# Connect.net
KiCad netlist of a schematic drawn in Altium Designer
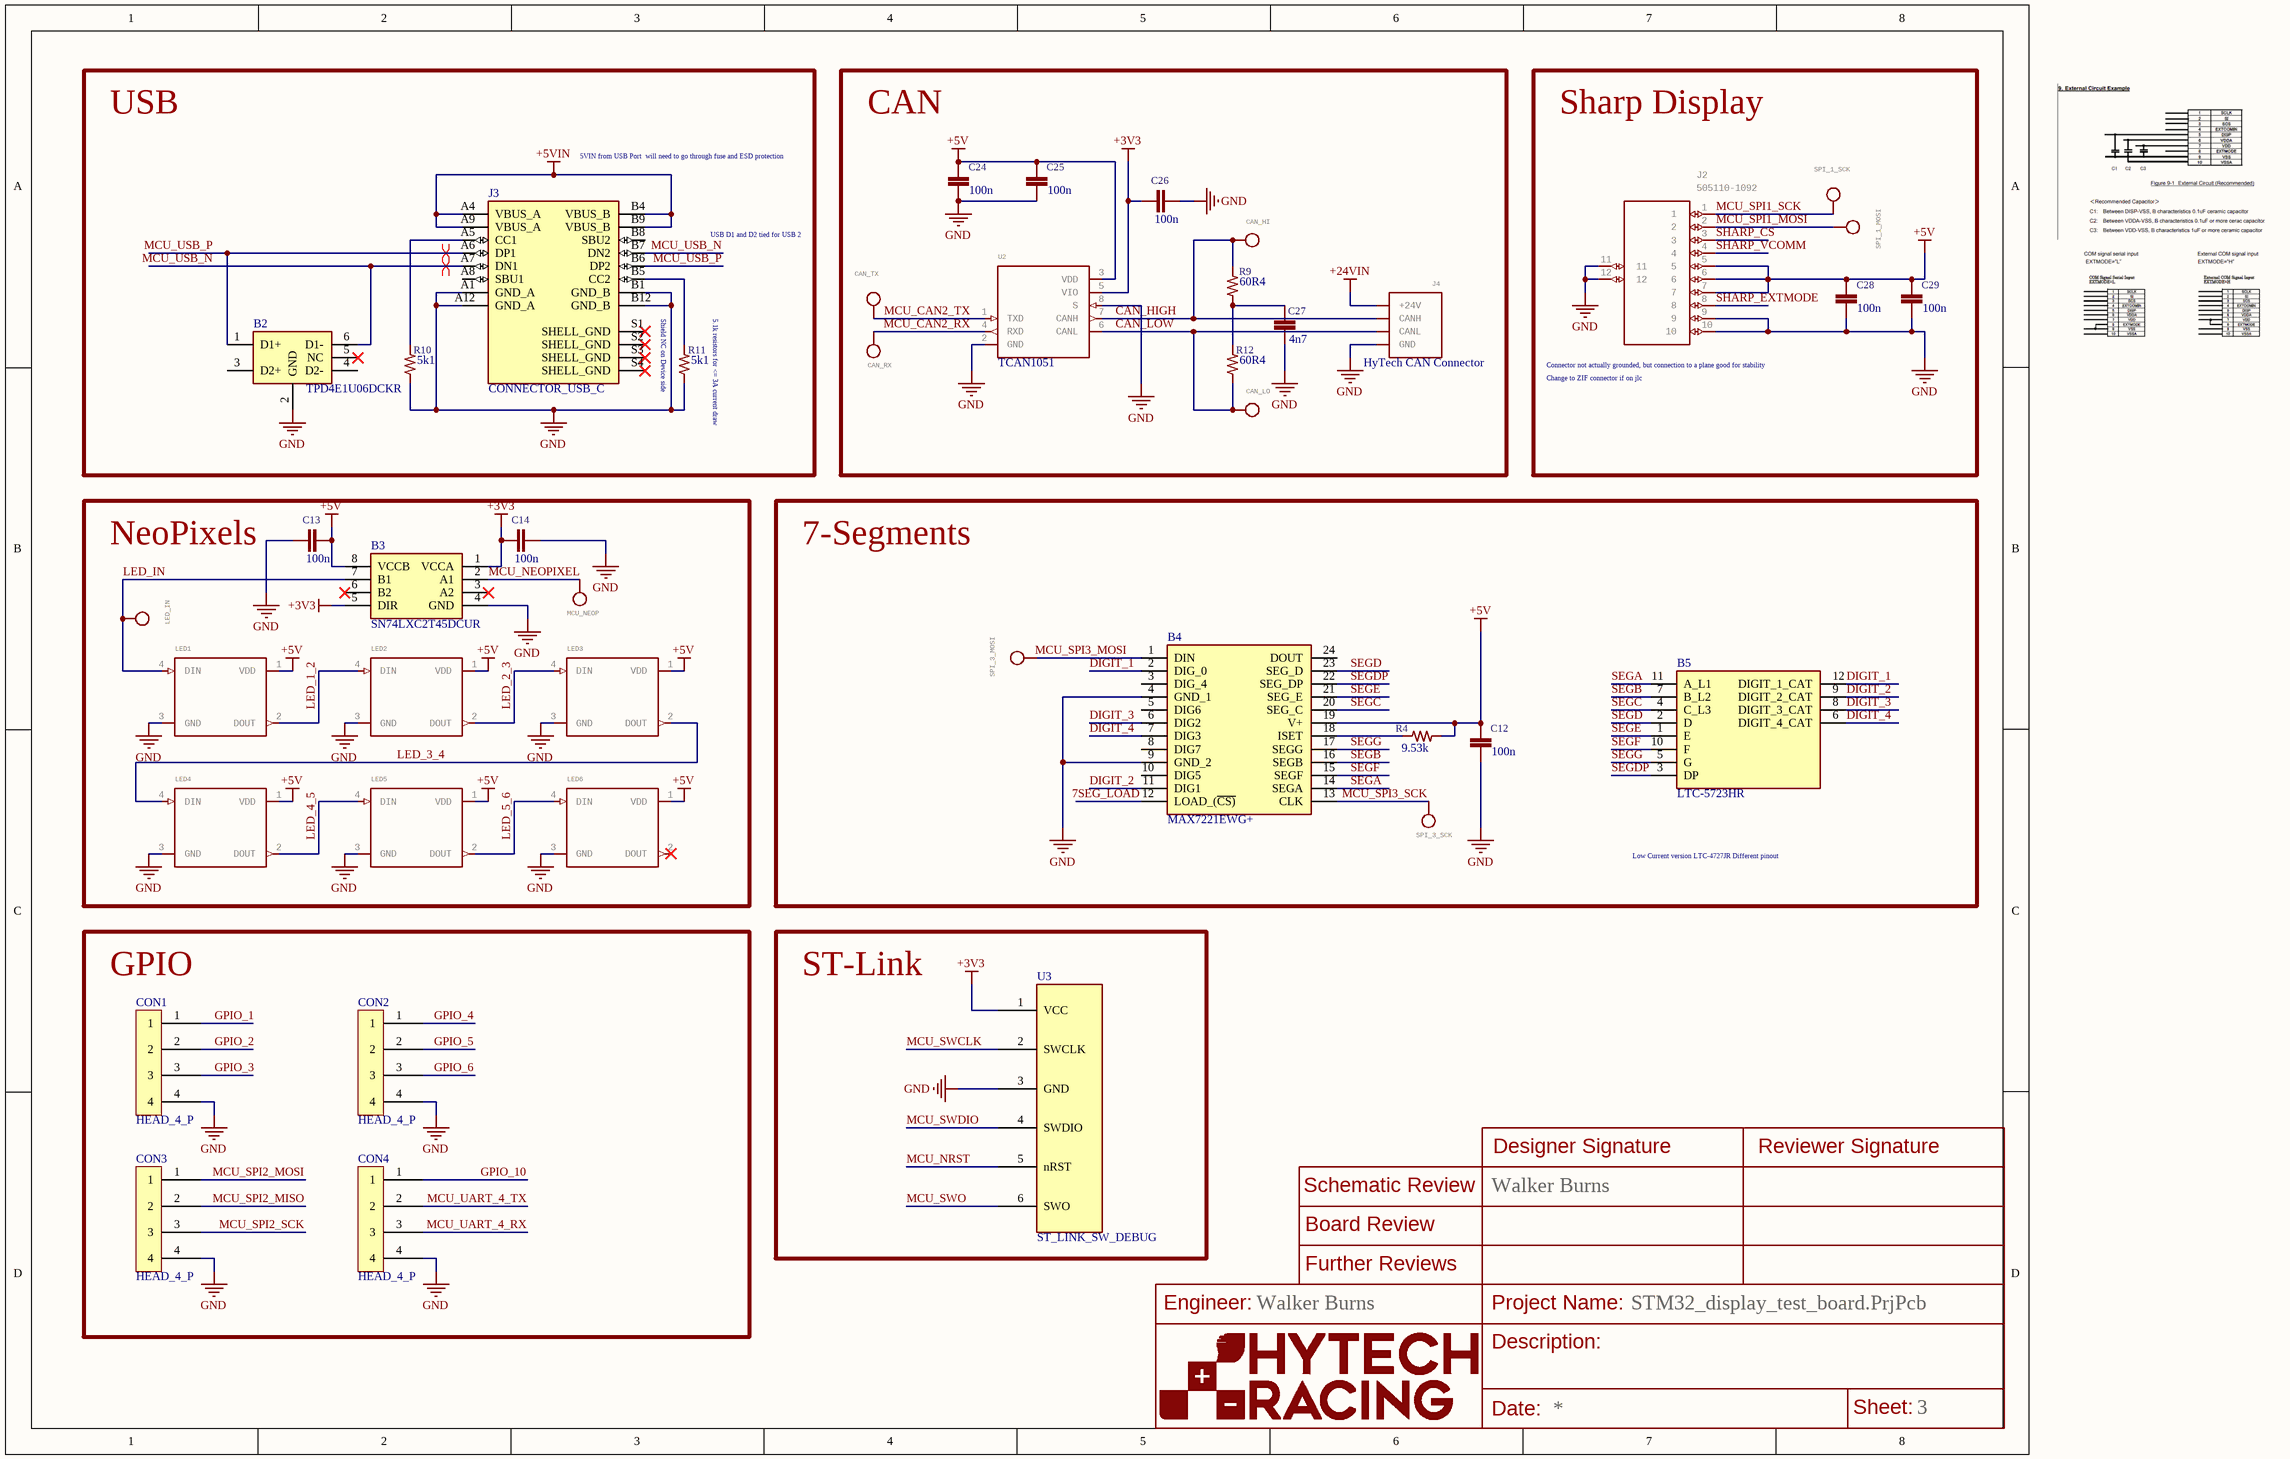
[diagram p0: Connect.SchDoc]

(export (version "E")
  (design (tool "Eeschema 10.0.6"))
  (components
    (comp (ref "B2")
      (value "TPD4E1U06DCKR")
      (footprint "SC-70-6")
      (description "Quad-Channel High-Speed ESD Protection Device")
      (fields (field (name "MOUSER PART NUMBER") "595-TPD4E1U06DCKR"))
      (libsource (lib "HyTechDevices") (part "TPD4E1U06DCKR"))
    )
    (comp (ref "B3")
      (value "SN74LXC2T45DCUR")
      (footprint "VSSOP-8")
      (fields (field (name "MOUSER PART NUMBER") "595-SN74LXC2T45DCUR"))
      (libsource (lib "HyTechDevices") (part "LEVEL_SHIFTER_3V3_TO_5V"))
    )
    (comp (ref "B4")
      (value "MAX7221EWG+")
      (footprint "SOIC-24")
      (description "MAX7221EWG+, LED Display Driver, 8-Digits 64-Segments, 4  5.5 V, 24-Pin SOIC W")
      (fields (field (name "MOUSER PART NUMBER") "700-MAX7221EWG"))
      (libsource (lib "HyTechDevices") (part "MAX7221EWG+"))
    )
    (comp (ref "B5")
      (value "LTC-5723HR")
      (footprint "7SEGMENT_DISP_12_P_TH")
      (description "LED Displays & Accessories 4 Digit, Red Normal Current, Common  Cathode")
      (fields
        (field (name "MOUSER PART NUMBER") "859-LTC-4627JR")
        (field (name "MANUFACTURER_PART_NUMBER") "LTC-4627JR")
      )
      (libsource (lib "HyTechDevices") (part "LED_7_SEGMENT_4_DIGIT"))
    )
    (comp (ref "C12")
      (value "100n")
      (footprint "0402_CAP")
      (fields
        (field (name "MANUFACTURER") "Yageo")
        (field (name "MPN") "CC0603KRX7R0BB104")
        (field (name "TOLERANCE") "10%")
      )
      (libsource (lib "HyTechDevices") (part "CAPACITOR_?_*0402"))
    )
    (comp (ref "C13")
      (value "100n")
      (footprint "0402_CAP")
      (fields
        (field (name "MANUFACTURER") "Yageo")
        (field (name "MPN") "CC0603KRX7R0BB104")
        (field (name "TOLERANCE") "10%")
      )
      (libsource (lib "") (part "CAPACITOR_?_*0402_1"))
    )
    (comp (ref "C14")
      (value "100n")
      (footprint "0402_CAP")
      (fields
        (field (name "MANUFACTURER") "Yageo")
        (field (name "MPN") "CC0603KRX7R0BB104")
        (field (name "TOLERANCE") "10%")
      )
      (libsource (lib "") (part "CAPACITOR_?_*0402_1"))
    )
    (comp (ref "C24")
      (value "100n")
      (footprint "0402_CAP")
      (fields
        (field (name "MANUFACTURER") "Yageo")
        (field (name "MPN") "CC0603KRX7R0BB104")
        (field (name "TOLERANCE") "10%")
      )
      (libsource (lib "HyTechDevices") (part "CAPACITOR_?_*0402"))
    )
    (comp (ref "C25")
      (value "100n")
      (footprint "0402_CAP")
      (fields
        (field (name "MANUFACTURER") "Yageo")
        (field (name "MPN") "CC0603KRX7R0BB104")
        (field (name "TOLERANCE") "10%")
      )
      (libsource (lib "HyTechDevices") (part "CAPACITOR_?_*0402"))
    )
    (comp (ref "C26")
      (value "100n")
      (footprint "0402_CAP")
      (fields
        (field (name "MANUFACTURER") "Yageo")
        (field (name "MPN") "CC0603KRX7R0BB104")
        (field (name "TOLERANCE") "10%")
      )
      (libsource (lib "") (part "CAPACITOR_?_*0402_1"))
    )
    (comp (ref "C27")
      (value "4n7")
      (footprint "0603-CAP")
      (fields
        (field (name "MANUFACTURER") "Yageo")
        (field (name "MPN") "CC0603KRX7R0BB104")
        (field (name "TOLERANCE") "10%")
      )
      (libsource (lib "HyTechDevices") (part "CAPACITOR_?_*0603"))
    )
    (comp (ref "C28")
      (value "100n")
      (footprint "0402_CAP")
      (fields
        (field (name "MANUFACTURER") "Yageo")
        (field (name "MPN") "CC0603KRX7R0BB104")
        (field (name "TOLERANCE") "10%")
      )
      (libsource (lib "HyTechDevices") (part "CAPACITOR_?_*0402"))
    )
    (comp (ref "C29")
      (value "100n")
      (footprint "0402_CAP")
      (fields
        (field (name "MANUFACTURER") "Yageo")
        (field (name "MPN") "CC0603KRX7R0BB104")
        (field (name "TOLERANCE") "10%")
      )
      (libsource (lib "HyTechDevices") (part "CAPACITOR_?_*0402"))
    )
    (comp (ref "CAN_HI")
      (value "Test Point for Probing")
      (footprint "5015")
      (fields (field (name "MANUFACTURER") "Keystone Electronics") (field (name "MPN") "5015"))
      (libsource (lib "HyTechDevices") (part "TEST_POINT"))
    )
    (comp (ref "CAN_LO")
      (value "Test Point for Probing")
      (footprint "5015")
      (fields (field (name "MANUFACTURER") "Keystone Electronics") (field (name "MPN") "5015"))
      (libsource (lib "HyTechDevices") (part "TEST_POINT"))
    )
    (comp (ref "CAN_RX")
      (value "Test Point for Probing")
      (footprint "5015")
      (fields (field (name "MANUFACTURER") "Keystone Electronics") (field (name "MPN") "5015"))
      (libsource (lib "HyTechDevices") (part "TEST_POINT"))
    )
    (comp (ref "CAN_TX")
      (value "Test Point for Probing")
      (footprint "5015")
      (fields (field (name "MANUFACTURER") "Keystone Electronics") (field (name "MPN") "5015"))
      (libsource (lib "HyTechDevices") (part "TEST_POINT"))
    )
    (comp (ref "CON1")
      (value "HEAD_4_P")
      (footprint "1X04")
      (description "4 Pin Standard Header")
      (libsource (lib "HyTechDevices") (part "CONNECTOR_HEADER_4"))
    )
    (comp (ref "CON2")
      (value "HEAD_4_P")
      (footprint "1X04")
      (description "4 Pin Standard Header")
      (libsource (lib "HyTechDevices") (part "CONNECTOR_HEADER_4"))
    )
    (comp (ref "CON3")
      (value "HEAD_4_P")
      (footprint "1X04")
      (description "4 Pin Standard Header")
      (libsource (lib "HyTechDevices") (part "CONNECTOR_HEADER_4"))
    )
    (comp (ref "CON4")
      (value "HEAD_4_P")
      (footprint "1X04")
      (description "4 Pin Standard Header")
      (libsource (lib "HyTechDevices") (part "CONNECTOR_HEADER_4"))
    )
    (comp (ref "FRAME3")
      (value "HyTech Racing Frame (ANSI Size A)  Prints on US Letter Landscape 8.5\" by 11\"   Fill Engineer/Description Fields with Text using the following settings:  Size: 0.1  Ratio: 8%  Line Distance: 50%  Font: Proportional  Layer: 94 Symbol")
      (fields (field (name "LIBRARYNAME") "HyTechFrames"))
      (libsource (lib "HyTechFrames") (part "FRAME"))
    )
    (comp (ref "J2")
      (value "505110-1092")
      (footprint "MOLEX_FPC_CLAMSHELL_10")
      (fields (field (name "MOUSER_PART_NUMBER") "538-505110-1092"))
      (libsource (lib "HyTechDevices") (part "CONNECTOR-10_MOLEX_FPC_CLAMSHELL"))
    )
    (comp (ref "J3")
      (value "CONNECTOR_USB_C")
      (footprint "VALCON_USB_C")
      (description "CSP-USC16-TR Valcon USB Type C Surface Mount PCB Socket")
      (fields (field (name "MF") "Valcon") (field (name "MP") "CSP-USC16-TR"))
      (libsource (lib "HyTechDevices") (part "CONNECTOR_USB_C"))
    )
    (comp (ref "J4")
      (value "HyTech CAN Connector")
      (footprint "MOLEX_MICROFIT_SMD_RIGHTANGLE_04_DUAL")
      (fields (field (name "MANUFACTURER") "Molex") (field (name "MPN") "0430450411"))
      (libsource (lib "HyTechDevices") (part "CONNECTOR-CAN_?_*μF_S_RA"))
    )
    (comp (ref "LED1")
      (value "IN-PI55QATPRPGPBPW-40  Neopixel RGBW LED  Datasheet")
      (footprint "NEOPIXEL")
      (fields (field (name "MANUFACTURER") "Inolux") (field (name "MPN") "IN-PI55QATPRPGPBPW-40"))
      (libsource (lib "HyTechDevices") (part "NEOPIXEL_*IN-PI55QATPRPGPBPW-40"))
    )
    (comp (ref "LED2")
      (value "IN-PI55QATPRPGPBPW-40  Neopixel RGBW LED  Datasheet")
      (footprint "NEOPIXEL")
      (fields (field (name "MANUFACTURER") "Inolux") (field (name "MPN") "IN-PI55QATPRPGPBPW-40"))
      (libsource (lib "HyTechDevices") (part "NEOPIXEL_*IN-PI55QATPRPGPBPW-40"))
    )
    (comp (ref "LED3")
      (value "IN-PI55QATPRPGPBPW-40  Neopixel RGBW LED  Datasheet")
      (footprint "NEOPIXEL")
      (fields (field (name "MANUFACTURER") "Inolux") (field (name "MPN") "IN-PI55QATPRPGPBPW-40"))
      (libsource (lib "HyTechDevices") (part "NEOPIXEL_*IN-PI55QATPRPGPBPW-40"))
    )
    (comp (ref "LED4")
      (value "IN-PI55QATPRPGPBPW-40  Neopixel RGBW LED  Datasheet")
      (footprint "NEOPIXEL")
      (fields (field (name "MANUFACTURER") "Inolux") (field (name "MPN") "IN-PI55QATPRPGPBPW-40"))
      (libsource (lib "HyTechDevices") (part "NEOPIXEL_*IN-PI55QATPRPGPBPW-40"))
    )
    (comp (ref "LED5")
      (value "IN-PI55QATPRPGPBPW-40  Neopixel RGBW LED  Datasheet")
      (footprint "NEOPIXEL")
      (fields (field (name "MANUFACTURER") "Inolux") (field (name "MPN") "IN-PI55QATPRPGPBPW-40"))
      (libsource (lib "HyTechDevices") (part "NEOPIXEL_*IN-PI55QATPRPGPBPW-40"))
    )
    (comp (ref "LED6")
      (value "IN-PI55QATPRPGPBPW-40  Neopixel RGBW LED  Datasheet")
      (footprint "NEOPIXEL")
      (fields (field (name "MANUFACTURER") "Inolux") (field (name "MPN") "IN-PI55QATPRPGPBPW-40"))
      (libsource (lib "HyTechDevices") (part "NEOPIXEL_*IN-PI55QATPRPGPBPW-40"))
    )
    (comp (ref "LED_IN")
      (value "Test Point for Probing")
      (footprint "5015")
      (fields (field (name "MANUFACTURER") "Keystone Electronics") (field (name "MPN") "5015"))
      (libsource (lib "HyTechDevices") (part "TEST_POINT"))
    )
    (comp (ref "MCU_NEOP")
      (value "Test Point for Probing")
      (footprint "5015")
      (fields (field (name "MANUFACTURER") "Keystone Electronics") (field (name "MPN") "5015"))
      (libsource (lib "HyTechDevices") (part "TEST_POINT"))
    )
    (comp (ref "R4")
      (value "9.53k")
      (footprint "0603-RES")
      (fields
        (field (name "MANUFACTURER") "Yageo")
        (field (name "MPN") "RC0603FR-070RL")
        (field (name "POWER") "0.1W")
      )
      (libsource (lib "HyTechDevices") (part "RESISTOR_?_*0603"))
    )
    (comp (ref "R9")
      (value "60R4")
      (footprint "0603-RES")
      (fields
        (field (name "MANUFACTURER") "Yageo")
        (field (name "MPN") "RC0603FR-070RL")
        (field (name "POWER") "0.1W")
      )
      (libsource (lib "") (part "RESISTOR_?_*0603_1"))
    )
    (comp (ref "R10")
      (value "5k1")
      (footprint "0603-RES")
      (fields
        (field (name "MANUFACTURER") "Yageo")
        (field (name "MPN") "RC0603FR-070RL")
        (field (name "POWER") "0.1W")
      )
      (libsource (lib "") (part "RESISTOR_?_*0603_1"))
    )
    (comp (ref "R11")
      (value "5k1")
      (footprint "0603-RES")
      (fields
        (field (name "MANUFACTURER") "Yageo")
        (field (name "MPN") "RC0603FR-070RL")
        (field (name "POWER") "0.1W")
      )
      (libsource (lib "") (part "RESISTOR_?_*0603_1"))
    )
    (comp (ref "R12")
      (value "60R4")
      (footprint "0603-RES")
      (fields
        (field (name "MANUFACTURER") "Yageo")
        (field (name "MPN") "RC0603FR-070RL")
        (field (name "POWER") "0.1W")
      )
      (libsource (lib "") (part "RESISTOR_?_*0603_1"))
    )
    (comp (ref "SPI_1_MOSI")
      (value "Test Point for Probing")
      (footprint "5015")
      (fields (field (name "MANUFACTURER") "Keystone Electronics") (field (name "MPN") "5015"))
      (libsource (lib "HyTechDevices") (part "TEST_POINT"))
    )
    (comp (ref "SPI_1_SCK")
      (value "Test Point for Probing")
      (footprint "5015")
      (fields (field (name "MANUFACTURER") "Keystone Electronics") (field (name "MPN") "5015"))
      (libsource (lib "HyTechDevices") (part "TEST_POINT"))
    )
    (comp (ref "SPI_3_MOSI")
      (value "Test Point for Probing")
      (footprint "5015")
      (fields (field (name "MANUFACTURER") "Keystone Electronics") (field (name "MPN") "5015"))
      (libsource (lib "HyTechDevices") (part "TEST_POINT"))
    )
    (comp (ref "SPI_3_SCK")
      (value "Test Point for Probing")
      (footprint "5015")
      (fields (field (name "MANUFACTURER") "Keystone Electronics") (field (name "MPN") "5015"))
      (libsource (lib "HyTechDevices") (part "TEST_POINT"))
    )
    (comp (ref "U2")
      (value "TCAN1051")
      (footprint "SOIC-08(NARROW,0-15\")")
      (fields (field (name "MANUFACTURER") "Texas Instruments") (field (name "MPN") "TCAN1051HGVDRQ1"))
      (libsource (lib "HyTechDevices") (part "TCAN1051*V-Q1"))
    )
    (comp (ref "U3")
      (value "ST_LINK_SW_DEBUG")
      (footprint "HEADER_6_P")
      (libsource (lib "HyTechDevices") (part "CONNECTOR_ST_LINK"))
    )
  )
  (nets
    (net (code "1") (name "+3V3") (class "Default")
      (node (ref "B3") (pin "1") (pinfunction "VCCA_1") (pintype "passive"))
      (node (ref "B3") (pin "5") (pinfunction "DIR_5") (pintype "passive"))
      (node (ref "C14") (pin "2") (pinfunction "2_2") (pintype "passive"))
      (node (ref "C26") (pin "2") (pinfunction "2_2") (pintype "passive"))
      (node (ref "U2") (pin "5") (pinfunction "VIO_5") (pintype "power_in"))
      (node (ref "U3") (pin "1") (pinfunction "VCC_1") (pintype "passive"))
    )
    (net (code "2") (name "+5V") (class "Default")
      (node (ref "B3") (pin "8") (pinfunction "VCCB_8") (pintype "passive"))
      (node (ref "B4") (pin "19") (pinfunction "V+_19") (pintype "passive"))
      (node (ref "C12") (pin "2") (pinfunction "2_2") (pintype "passive"))
      (node (ref "C13") (pin "1") (pinfunction "1_1") (pintype "passive"))
      (node (ref "C24") (pin "2") (pinfunction "2_2") (pintype "passive"))
      (node (ref "C25") (pin "2") (pinfunction "2_2") (pintype "passive"))
      (node (ref "C28") (pin "2") (pinfunction "2_2") (pintype "passive"))
      (node (ref "C29") (pin "2") (pinfunction "2_2") (pintype "passive"))
      (node (ref "J2") (pin "5") (pinfunction "5_5") (pintype "bidirectional"))
      (node (ref "J2") (pin "6") (pinfunction "6_6") (pintype "bidirectional"))
      (node (ref "J2") (pin "7") (pinfunction "7_7") (pintype "bidirectional"))
      (node (ref "LED1") (pin "1") (pinfunction "VDD_1") (pintype "power_in"))
      (node (ref "LED2") (pin "1") (pinfunction "VDD_1") (pintype "power_in"))
      (node (ref "LED3") (pin "1") (pinfunction "VDD_1") (pintype "power_in"))
      (node (ref "LED4") (pin "1") (pinfunction "VDD_1") (pintype "power_in"))
      (node (ref "LED5") (pin "1") (pinfunction "VDD_1") (pintype "power_in"))
      (node (ref "LED6") (pin "1") (pinfunction "VDD_1") (pintype "power_in"))
      (node (ref "R4") (pin "2") (pinfunction "2_2") (pintype "passive"))
      (node (ref "U2") (pin "3") (pinfunction "VDD_3") (pintype "power_in"))
    )
    (net (code "3") (name "+5VIN") (class "Default")
      (node (ref "J3") (pin "A4") (pinfunction "VBUS_A_A4") (pintype "power_in"))
      (node (ref "J3") (pin "A9") (pinfunction "VBUS_A_A9") (pintype "power_in"))
      (node (ref "J3") (pin "B4") (pinfunction "VBUS_B_B4") (pintype "power_in"))
      (node (ref "J3") (pin "B9") (pinfunction "VBUS_B_B9") (pintype "power_in"))
    )
    (net (code "4") (name "+24VIN") (class "Default")
      (node (ref "J4") (pin "1") (pinfunction "+24V_1") (pintype "power_in"))
    )
    (net (code "5") (name "/7SEG_LOAD") (class "Default")
      (node (ref "B4") (pin "12") (pinfunction "LOAD_(~{CS)}_12") (pintype "passive"))
    )
    (net (code "6") (name "/CAN_HIGH") (class "Default")
      (node (ref "CAN_HI") (pin "1") (pinfunction "1_1") (pintype "passive"))
      (node (ref "J4") (pin "4") (pinfunction "CANH_4") (pintype "bidirectional"))
      (node (ref "R9") (pin "1") (pinfunction "1_1") (pintype "passive"))
      (node (ref "U2") (pin "7") (pinfunction "CANH_7") (pintype "output"))
    )
    (net (code "7") (name "/CAN_LOW") (class "Default")
      (node (ref "CAN_LO") (pin "1") (pinfunction "1_1") (pintype "passive"))
      (node (ref "J4") (pin "3") (pinfunction "CANL_3") (pintype "bidirectional"))
      (node (ref "R12") (pin "2") (pinfunction "2_2") (pintype "passive"))
      (node (ref "U2") (pin "6") (pinfunction "CANL_6") (pintype "bidirectional"))
    )
    (net (code "8") (name "/DIGIT_1") (class "Default")
      (node (ref "B4") (pin "2") (pinfunction "DIG_0_2") (pintype "passive"))
      (node (ref "B5") (pin "12") (pinfunction "DIGIT_1_CAT_12") (pintype "passive"))
    )
    (net (code "9") (name "/DIGIT_2") (class "Default")
      (node (ref "B4") (pin "11") (pinfunction "DIG1_11") (pintype "passive"))
      (node (ref "B5") (pin "9") (pinfunction "DIGIT_2_CAT_9") (pintype "passive"))
    )
    (net (code "10") (name "/DIGIT_3") (class "Default")
      (node (ref "B4") (pin "6") (pinfunction "DIG2_6") (pintype "passive"))
      (node (ref "B5") (pin "8") (pinfunction "DIGIT_3_CAT_8") (pintype "passive"))
    )
    (net (code "11") (name "/DIGIT_4") (class "Default")
      (node (ref "B4") (pin "7") (pinfunction "DIG3_7") (pintype "passive"))
      (node (ref "B5") (pin "6") (pinfunction "DIGIT_4_CAT_6") (pintype "passive"))
    )
    (net (code "12") (name "/GPIO_1") (class "Default")
      (node (ref "CON1") (pin "1") (pinfunction "1_1") (pintype "passive"))
    )
    (net (code "13") (name "/GPIO_2") (class "Default")
      (node (ref "CON1") (pin "2") (pinfunction "2_2") (pintype "passive"))
    )
    (net (code "14") (name "/GPIO_3") (class "Default")
      (node (ref "CON1") (pin "3") (pinfunction "3_3") (pintype "passive"))
    )
    (net (code "15") (name "/GPIO_4") (class "Default")
      (node (ref "CON2") (pin "1") (pinfunction "1_1") (pintype "passive"))
    )
    (net (code "16") (name "/GPIO_5") (class "Default")
      (node (ref "CON2") (pin "2") (pinfunction "2_2") (pintype "passive"))
    )
    (net (code "17") (name "/GPIO_6") (class "Default")
      (node (ref "CON2") (pin "3") (pinfunction "3_3") (pintype "passive"))
    )
    (net (code "18") (name "/GPIO_10") (class "Default")
      (node (ref "CON4") (pin "1") (pinfunction "1_1") (pintype "passive"))
    )
    (net (code "19") (name "/LED_1_2") (class "Default")
      (node (ref "LED1") (pin "2") (pinfunction "DOUT_2") (pintype "output"))
      (node (ref "LED2") (pin "4") (pinfunction "DIN_4") (pintype "input"))
    )
    (net (code "20") (name "/LED_2_3") (class "Default")
      (node (ref "LED2") (pin "2") (pinfunction "DOUT_2") (pintype "output"))
      (node (ref "LED3") (pin "4") (pinfunction "DIN_4") (pintype "input"))
    )
    (net (code "21") (name "/LED_3_4") (class "Default")
      (node (ref "LED3") (pin "2") (pinfunction "DOUT_2") (pintype "output"))
      (node (ref "LED4") (pin "4") (pinfunction "DIN_4") (pintype "input"))
    )
    (net (code "22") (name "/LED_4_5") (class "Default")
      (node (ref "LED4") (pin "2") (pinfunction "DOUT_2") (pintype "output"))
      (node (ref "LED5") (pin "4") (pinfunction "DIN_4") (pintype "input"))
    )
    (net (code "23") (name "/LED_5_6") (class "Default")
      (node (ref "LED5") (pin "2") (pinfunction "DOUT_2") (pintype "output"))
      (node (ref "LED6") (pin "4") (pinfunction "DIN_4") (pintype "input"))
    )
    (net (code "24") (name "/LED_IN") (class "Default")
      (node (ref "B3") (pin "7") (pinfunction "B1_7") (pintype "passive"))
      (node (ref "LED1") (pin "4") (pinfunction "DIN_4") (pintype "input"))
      (node (ref "LED_IN") (pin "1") (pinfunction "1_1") (pintype "passive"))
    )
    (net (code "25") (name "/MCU_CAN2_RX") (class "Default")
      (node (ref "CAN_RX") (pin "1") (pinfunction "1_1") (pintype "passive"))
      (node (ref "U2") (pin "4") (pinfunction "RXD_4") (pintype "output"))
    )
    (net (code "26") (name "/MCU_CAN2_TX") (class "Default")
      (node (ref "CAN_TX") (pin "1") (pinfunction "1_1") (pintype "passive"))
      (node (ref "U2") (pin "1") (pinfunction "TXD_1") (pintype "input"))
    )
    (net (code "27") (name "/MCU_NEOPIXEL") (class "Default")
      (node (ref "B3") (pin "2") (pinfunction "A1_2") (pintype "passive"))
      (node (ref "MCU_NEOP") (pin "1") (pinfunction "1_1") (pintype "passive"))
    )
    (net (code "28") (name "/MCU_NRST") (class "Default")
      (node (ref "U3") (pin "5") (pinfunction "nRST_5") (pintype "passive"))
    )
    (net (code "29") (name "/MCU_SPI1_MOSI") (class "Default")
      (node (ref "J2") (pin "2") (pinfunction "2_2") (pintype "bidirectional"))
      (node (ref "SPI_1_MOSI") (pin "1") (pinfunction "1_1") (pintype "passive"))
    )
    (net (code "30") (name "/MCU_SPI1_SCK") (class "Default")
      (node (ref "J2") (pin "1") (pinfunction "1_1") (pintype "bidirectional"))
      (node (ref "SPI_1_SCK") (pin "1") (pinfunction "1_1") (pintype "passive"))
    )
    (net (code "31") (name "/MCU_SPI2_MISO") (class "Default")
      (node (ref "CON3") (pin "2") (pinfunction "2_2") (pintype "passive"))
    )
    (net (code "32") (name "/MCU_SPI2_MOSI") (class "Default")
      (node (ref "CON3") (pin "1") (pinfunction "1_1") (pintype "passive"))
    )
    (net (code "33") (name "/MCU_SPI2_SCK") (class "Default")
      (node (ref "CON3") (pin "3") (pinfunction "3_3") (pintype "passive"))
    )
    (net (code "34") (name "/MCU_SPI3_MOSI") (class "Default")
      (node (ref "B4") (pin "1") (pinfunction "DIN_1") (pintype "passive"))
      (node (ref "SPI_3_MOSI") (pin "1") (pinfunction "1_1") (pintype "passive"))
    )
    (net (code "35") (name "/MCU_SPI3_SCK") (class "Default")
      (node (ref "B4") (pin "13") (pinfunction "CLK_13") (pintype "passive"))
      (node (ref "SPI_3_SCK") (pin "1") (pinfunction "1_1") (pintype "passive"))
    )
    (net (code "36") (name "/MCU_SWCLK") (class "Default")
      (node (ref "U3") (pin "2") (pinfunction "SWCLK_2") (pintype "passive"))
    )
    (net (code "37") (name "/MCU_SWDIO") (class "Default")
      (node (ref "U3") (pin "4") (pinfunction "SWDIO_4") (pintype "passive"))
    )
    (net (code "38") (name "/MCU_SWO") (class "Default")
      (node (ref "U3") (pin "6") (pinfunction "SWO_6") (pintype "passive"))
    )
    (net (code "39") (name "/MCU_UART_4_RX") (class "Default")
      (node (ref "CON4") (pin "3") (pinfunction "3_3") (pintype "passive"))
    )
    (net (code "40") (name "/MCU_UART_4_TX") (class "Default")
      (node (ref "CON4") (pin "2") (pinfunction "2_2") (pintype "passive"))
    )
    (net (code "41") (name "/MCU_USB_N") (class "Default")
      (node (ref "B2") (pin "6") (pinfunction "D1-_6") (pintype "passive"))
      (node (ref "J3") (pin "A7") (pinfunction "DN1_A7") (pintype "bidirectional"))
      (node (ref "J3") (pin "B7") (pinfunction "DN2_B7") (pintype "bidirectional"))
    )
    (net (code "42") (name "/MCU_USB_P") (class "Default")
      (node (ref "B2") (pin "1") (pinfunction "D1+_1") (pintype "passive"))
      (node (ref "J3") (pin "A6") (pinfunction "DP1_A6") (pintype "bidirectional"))
      (node (ref "J3") (pin "B6") (pinfunction "DP2_B6") (pintype "bidirectional"))
    )
    (net (code "43") (name "/SEGA") (class "Default")
      (node (ref "B4") (pin "14") (pinfunction "SEGA_14") (pintype "passive"))
      (node (ref "B5") (pin "11") (pinfunction "A_L1_11") (pintype "passive"))
    )
    (net (code "44") (name "/SEGB") (class "Default")
      (node (ref "B4") (pin "16") (pinfunction "SEGB_16") (pintype "passive"))
      (node (ref "B5") (pin "7") (pinfunction "B_L2_7") (pintype "passive"))
    )
    (net (code "45") (name "/SEGC") (class "Default")
      (node (ref "B4") (pin "20") (pinfunction "SEG_C_20") (pintype "passive"))
      (node (ref "B5") (pin "4") (pinfunction "C_L3_4") (pintype "passive"))
    )
    (net (code "46") (name "/SEGD") (class "Default")
      (node (ref "B4") (pin "23") (pinfunction "SEG_D_23") (pintype "passive"))
      (node (ref "B5") (pin "2") (pinfunction "D_2") (pintype "passive"))
    )
    (net (code "47") (name "/SEGDP") (class "Default")
      (node (ref "B4") (pin "22") (pinfunction "SEG_DP_22") (pintype "passive"))
      (node (ref "B5") (pin "3") (pinfunction "DP_3") (pintype "passive"))
    )
    (net (code "48") (name "/SEGE") (class "Default")
      (node (ref "B4") (pin "21") (pinfunction "SEG_E_21") (pintype "passive"))
      (node (ref "B5") (pin "1") (pinfunction "E_1") (pintype "passive"))
    )
    (net (code "49") (name "/SEGF") (class "Default")
      (node (ref "B4") (pin "15") (pinfunction "SEGF_15") (pintype "passive"))
      (node (ref "B5") (pin "10") (pinfunction "F_10") (pintype "passive"))
    )
    (net (code "50") (name "/SEGG") (class "Default")
      (node (ref "B4") (pin "17") (pinfunction "SEGG_17") (pintype "passive"))
      (node (ref "B5") (pin "5") (pinfunction "G_5") (pintype "passive"))
    )
    (net (code "51") (name "/SHARP_CS") (class "Default")
      (node (ref "J2") (pin "3") (pinfunction "3_3") (pintype "bidirectional"))
    )
    (net (code "52") (name "/SHARP_EXTMODE") (class "Default")
      (node (ref "J2") (pin "8") (pinfunction "8_8") (pintype "bidirectional"))
    )
    (net (code "53") (name "/SHARP_VCOMM") (class "Default")
      (node (ref "J2") (pin "4") (pinfunction "4_4") (pintype "bidirectional"))
    )
    (net (code "54") (name "GND") (class "Default")
      (node (ref "B2") (pin "2") (pinfunction "GND_2") (pintype "passive"))
      (node (ref "B3") (pin "4") (pinfunction "GND_4") (pintype "passive"))
      (node (ref "B4") (pin "4") (pinfunction "GND_1_4") (pintype "passive"))
      (node (ref "B4") (pin "9") (pinfunction "GND_2_9") (pintype "passive"))
      (node (ref "C12") (pin "1") (pinfunction "1_1") (pintype "passive"))
      (node (ref "C13") (pin "2") (pinfunction "2_2") (pintype "passive"))
      (node (ref "C14") (pin "1") (pinfunction "1_1") (pintype "passive"))
      (node (ref "C24") (pin "1") (pinfunction "1_1") (pintype "passive"))
      (node (ref "C25") (pin "1") (pinfunction "1_1") (pintype "passive"))
      (node (ref "C26") (pin "1") (pinfunction "1_1") (pintype "passive"))
      (node (ref "C27") (pin "1") (pinfunction "1_1") (pintype "passive"))
      (node (ref "C28") (pin "1") (pinfunction "1_1") (pintype "passive"))
      (node (ref "C29") (pin "1") (pinfunction "1_1") (pintype "passive"))
      (node (ref "CON1") (pin "4") (pinfunction "4_4") (pintype "passive"))
      (node (ref "CON2") (pin "4") (pinfunction "4_4") (pintype "passive"))
      (node (ref "CON3") (pin "4") (pinfunction "4_4") (pintype "passive"))
      (node (ref "CON4") (pin "4") (pinfunction "4_4") (pintype "passive"))
      (node (ref "J2") (pin "10") (pinfunction "10_10") (pintype "bidirectional"))
      (node (ref "J2") (pin "11") (pinfunction "11_11") (pintype "bidirectional"))
      (node (ref "J2") (pin "12") (pinfunction "12_12") (pintype "bidirectional"))
      (node (ref "J2") (pin "9") (pinfunction "9_9") (pintype "bidirectional"))
      (node (ref "J3") (pin "A1") (pinfunction "GND_A_A1") (pintype "power_in"))
      (node (ref "J3") (pin "A12") (pinfunction "GND_A_A12") (pintype "power_in"))
      (node (ref "J3") (pin "B1") (pinfunction "GND_B_B1") (pintype "power_in"))
      (node (ref "J3") (pin "B12") (pinfunction "GND_B_B12") (pintype "power_in"))
      (node (ref "J4") (pin "2") (pinfunction "GND_2") (pintype "power_in"))
      (node (ref "LED1") (pin "3") (pinfunction "GND_3") (pintype "power_in"))
      (node (ref "LED2") (pin "3") (pinfunction "GND_3") (pintype "power_in"))
      (node (ref "LED3") (pin "3") (pinfunction "GND_3") (pintype "power_in"))
      (node (ref "LED4") (pin "3") (pinfunction "GND_3") (pintype "power_in"))
      (node (ref "LED5") (pin "3") (pinfunction "GND_3") (pintype "power_in"))
      (node (ref "LED6") (pin "3") (pinfunction "GND_3") (pintype "power_in"))
      (node (ref "R10") (pin "2") (pinfunction "2_2") (pintype "passive"))
      (node (ref "R11") (pin "2") (pinfunction "2_2") (pintype "passive"))
      (node (ref "U2") (pin "2") (pinfunction "GND_2") (pintype "power_in"))
      (node (ref "U2") (pin "8") (pinfunction "S_8") (pintype "input"))
      (node (ref "U3") (pin "3") (pinfunction "GND_3") (pintype "passive"))
    )
    (net (code "55") (name "Net-(B4-ISET)") (class "Default")
      (node (ref "B4") (pin "18") (pinfunction "ISET_18") (pintype "passive"))
      (node (ref "R4") (pin "1") (pinfunction "1_1") (pintype "passive"))
    )
    (net (code "56") (name "Net-(C27-Pad2)") (class "Default")
      (node (ref "C27") (pin "2") (pinfunction "2_2") (pintype "passive"))
      (node (ref "R12") (pin "1") (pinfunction "1_1") (pintype "passive"))
      (node (ref "R9") (pin "2") (pinfunction "2_2") (pintype "passive"))
    )
    (net (code "57") (name "Net-(J3-CC1)") (class "Default")
      (node (ref "J3") (pin "A5") (pinfunction "CC1_A5") (pintype "bidirectional"))
      (node (ref "R10") (pin "1") (pinfunction "1_1") (pintype "passive"))
    )
    (net (code "58") (name "Net-(J3-CC2)") (class "Default")
      (node (ref "J3") (pin "B5") (pinfunction "CC2_B5") (pintype "bidirectional"))
      (node (ref "R11") (pin "1") (pinfunction "1_1") (pintype "passive"))
    )
    (net (code "59") (name "unconnected-(B2-D2+-Pad3)") (class "Default")
      (node (ref "B2") (pin "3") (pinfunction "D2+_3") (pintype "passive"))
    )
    (net (code "60") (name "unconnected-(B2-D2--Pad4)") (class "Default")
      (node (ref "B2") (pin "4") (pinfunction "D2-_4") (pintype "passive"))
    )
    (net (code "61") (name "unconnected-(B2-NC-Pad5)") (class "Default")
      (node (ref "B2") (pin "5") (pinfunction "NC_5") (pintype "passive+no_connect"))
    )
    (net (code "62") (name "unconnected-(B3-A2-Pad3)") (class "Default")
      (node (ref "B3") (pin "3") (pinfunction "A2_3") (pintype "passive+no_connect"))
    )
    (net (code "63") (name "unconnected-(B3-B2-Pad6)") (class "Default")
      (node (ref "B3") (pin "6") (pinfunction "B2_6") (pintype "passive+no_connect"))
    )
    (net (code "64") (name "unconnected-(B4-DIG5-Pad10)") (class "Default")
      (node (ref "B4") (pin "10") (pinfunction "DIG5_10") (pintype "passive"))
    )
    (net (code "65") (name "unconnected-(B4-DIG6-Pad5)") (class "Default")
      (node (ref "B4") (pin "5") (pinfunction "DIG6_5") (pintype "passive"))
    )
    (net (code "66") (name "unconnected-(B4-DIG7-Pad8)") (class "Default")
      (node (ref "B4") (pin "8") (pinfunction "DIG7_8") (pintype "passive"))
    )
    (net (code "67") (name "unconnected-(B4-DIG_4-Pad3)") (class "Default")
      (node (ref "B4") (pin "3") (pinfunction "DIG_4_3") (pintype "passive"))
    )
    (net (code "68") (name "unconnected-(B4-DOUT-Pad24)") (class "Default")
      (node (ref "B4") (pin "24") (pinfunction "DOUT_24") (pintype "passive"))
    )
    (net (code "69") (name "unconnected-(J3-SBU1-PadA8)") (class "Default")
      (node (ref "J3") (pin "A8") (pinfunction "SBU1_A8") (pintype "bidirectional"))
    )
    (net (code "70") (name "unconnected-(J3-SBU2-PadB8)") (class "Default")
      (node (ref "J3") (pin "B8") (pinfunction "SBU2_B8") (pintype "bidirectional"))
    )
    (net (code "71") (name "unconnected-(J3-SHELL_GND-PadS1)") (class "Default")
      (node (ref "J3") (pin "S1") (pinfunction "SHELL_GND_S1") (pintype "power_in+no_connect"))
    )
    (net (code "72") (name "unconnected-(J3-SHELL_GND-PadS2)") (class "Default")
      (node (ref "J3") (pin "S2") (pinfunction "SHELL_GND_S2") (pintype "power_in+no_connect"))
    )
    (net (code "73") (name "unconnected-(J3-SHELL_GND-PadS3)") (class "Default")
      (node (ref "J3") (pin "S3") (pinfunction "SHELL_GND_S3") (pintype "power_in+no_connect"))
    )
    (net (code "74") (name "unconnected-(J3-SHELL_GND-PadS4)") (class "Default")
      (node (ref "J3") (pin "S4") (pinfunction "SHELL_GND_S4") (pintype "power_in+no_connect"))
    )
    (net (code "75") (name "unconnected-(LED6-DOUT-Pad2)") (class "Default")
      (node (ref "LED6") (pin "2") (pinfunction "DOUT_2") (pintype "output+no_connect"))
    )
  )
)
